# ST1S40IDR.net
KiCad netlist of a schematic drawn in Altium Designer
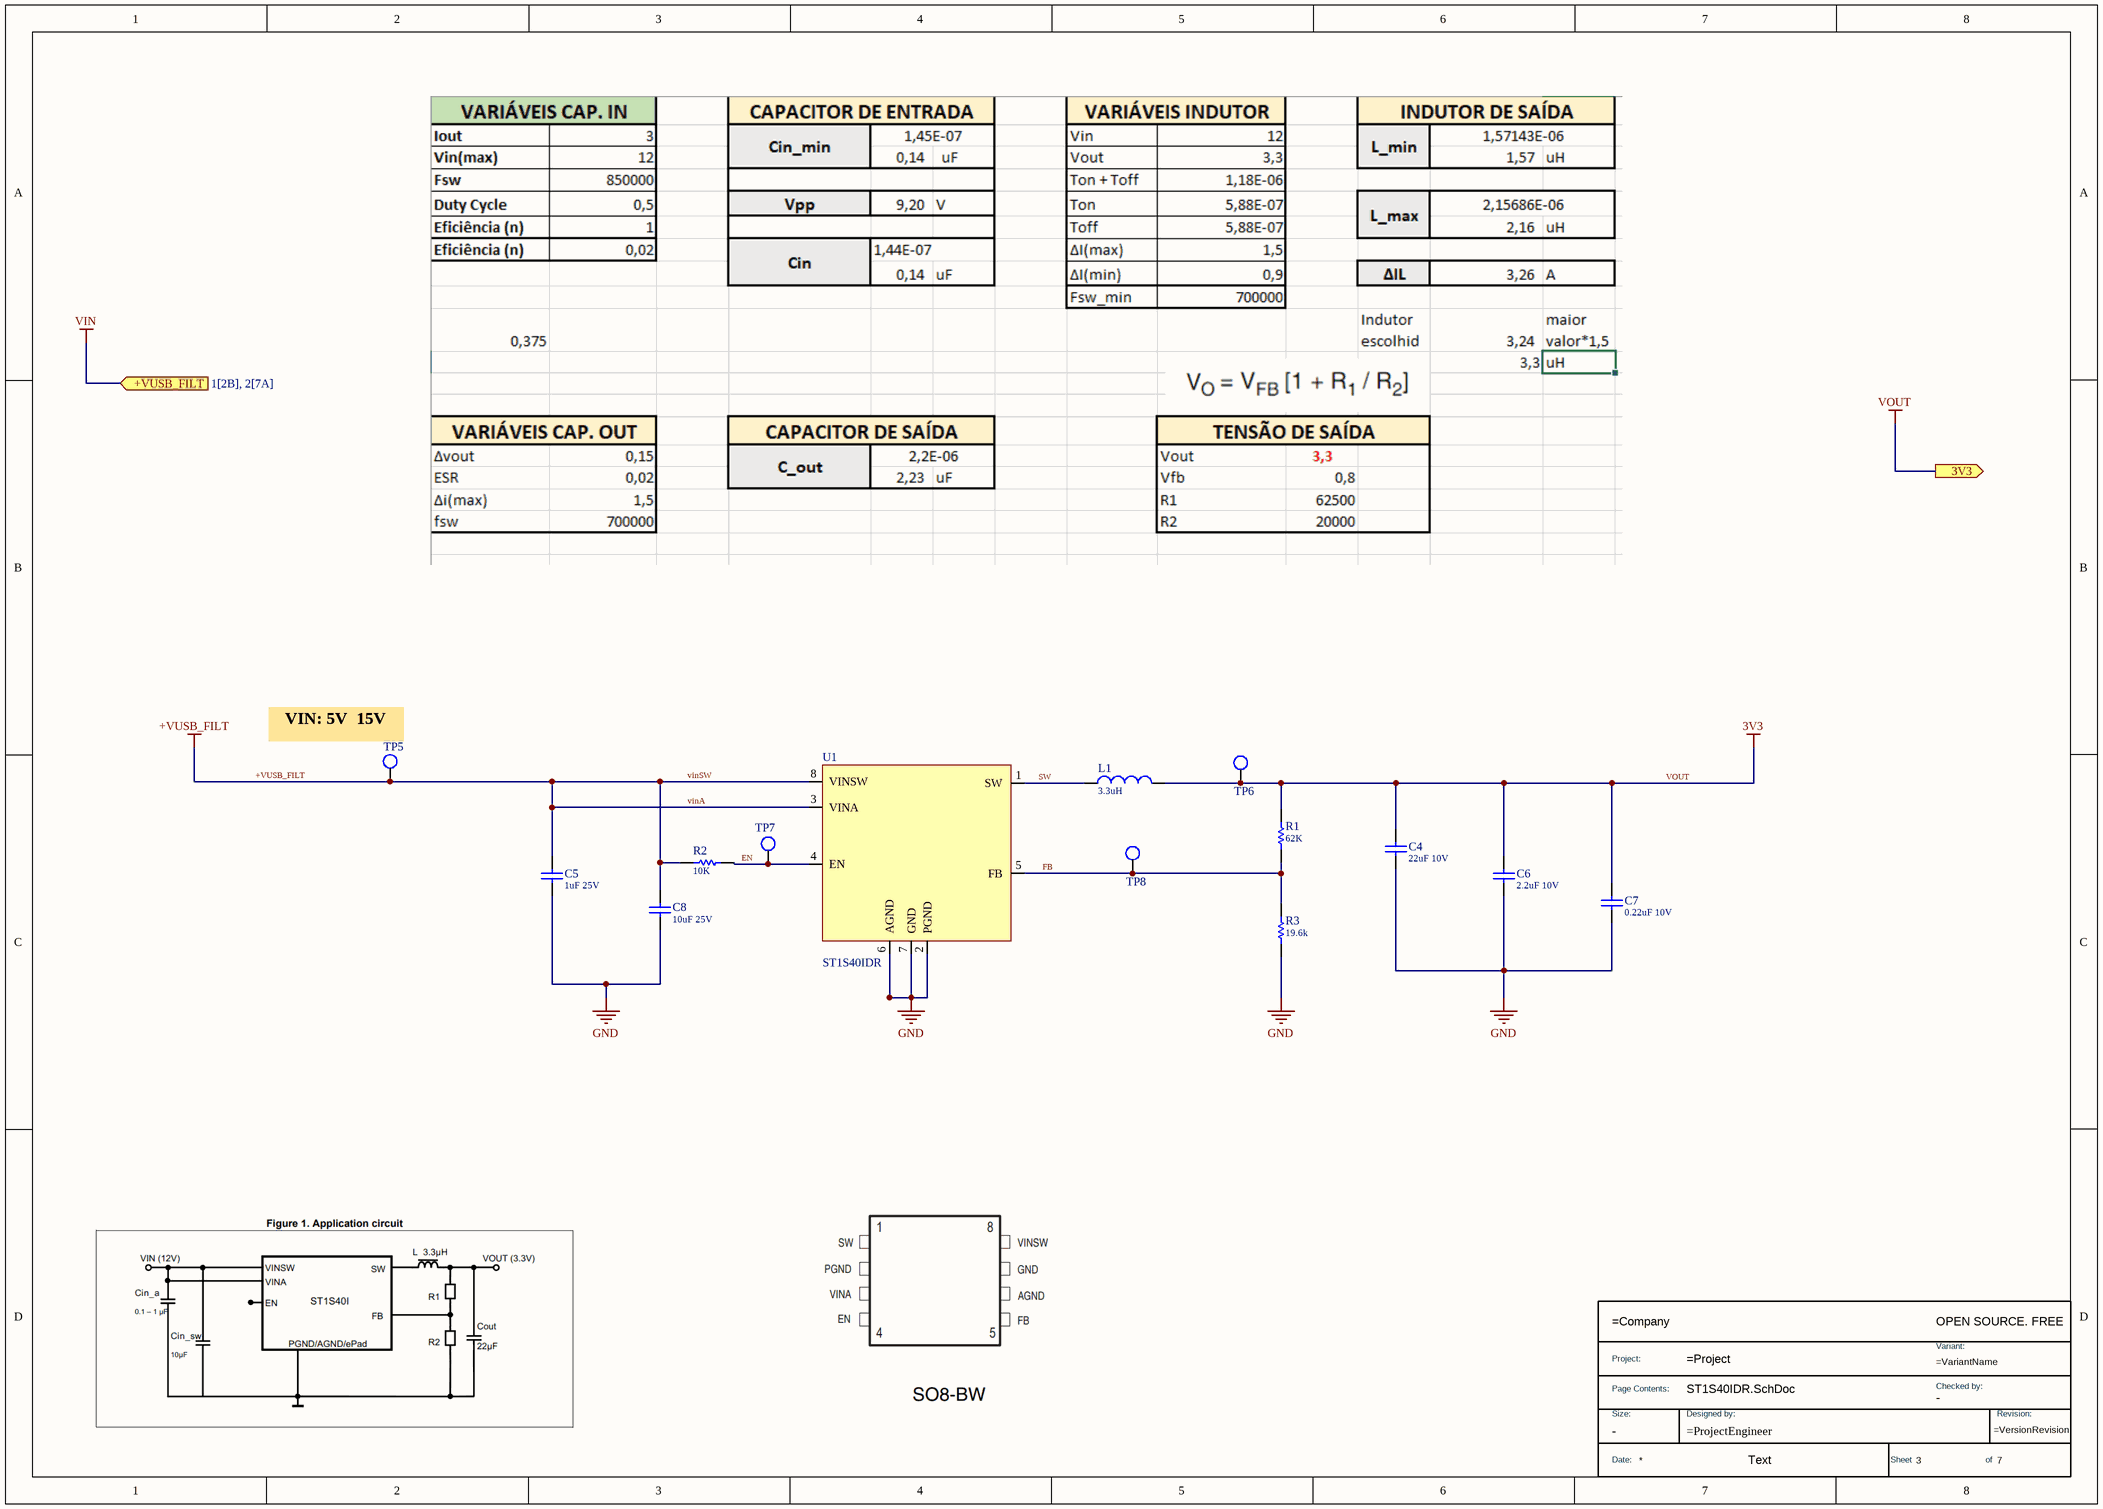
[diagram p0: ST1S40IDR.SchDoc]

(export (version "E")
  (design (tool "Eeschema 10.0.6"))
  (components
    (comp (ref "C4")
      (value "CL21A226MPQNNNE")
      (footprint "0805")
      (description "CAP CER 22UF 10V X5R 0805")
      (fields (field (name "MANUFACTURER") "Samsung Electro-Mechanics") (field (name "VALOR") "22uF 10V"))
      (libsource (lib "OBDH_Ed02") (part "CL21A226MPQNNNE"))
    )
    (comp (ref "C5")
      (value "CL21B105KAFNNNE")
      (footprint "CAP_0805")
      (description "CAP CER 1UF 25V X7R 0805")
      (fields (field (name "MANUFACTURER") "Samsung Electro-Mechanics") (field (name "VALOR") "1uF 25V"))
      (libsource (lib "OBDH_Ed02") (part "CL21B105KAFNNNE"))
    )
    (comp (ref "C6")
      (value "CL21B225KAFNNNE")
      (footprint "0805")
      (description "CAP CER 2.2UF 10V X5R 0805")
      (fields (field (name "MANUFACTURER") "Samsung Electro-Mechanics") (field (name "VALOR") "2.2uF 10V"))
      (libsource (lib "OBDH_Ed02") (part "CL21B225KAFNNNE"))
    )
    (comp (ref "C7")
      (value "CC0805KRX7R6BB224")
      (footprint "0805")
      (description "CAP CER 0.22uF 10V X5R 0805")
      (fields (field (name "MANUFACTURER") "YAGEO") (field (name "VALOR") "0.22uF 10V"))
      (libsource (lib "OBDH_Ed02") (part "CC0805KRX7R6BB224"))
    )
    (comp (ref "C8")
      (value "CL21A106KAYNNNE")
      (footprint "CAP_0805")
      (description "CAP CER 10UF 25V X5R 0805")
      (fields (field (name "MANUFACTURER") "Samsung Electro-Mechanics") (field (name "VALOR") "10uF 25V"))
      (libsource (lib "OBDH_Ed02") (part "CL21A106KAYNNNE"))
    )
    (comp (ref "L1")
      (value "3.3uH")
      (footprint "IND_6.1-4")
      (description "FIXED IND 3.3UH 4.2A 35.1MOHM SM")
      (fields (field (name "MANUFACTURER PART NUMBER") "VLS5045EX-3R3N-H"))
      (libsource (lib "OBDH_Ed02") (part "VLS5045EX-3R3N-H"))
    )
    (comp (ref "R1")
      (value "CRCW080562K0JNEA")
      (footprint "RES_0805")
      (description "RES SMD 62K OHM 5% 1/8W 0805")
      (fields (field (name "MANUFACTURER") "YAGEO") (field (name "VALOR") "62K"))
      (libsource (lib "OBDH_Ed02") (part "CRCW080562K0JNEA"))
    )
    (comp (ref "R2")
      (value "AF0805JR-0710KL")
      (footprint "RES_0805")
      (description "RES SMD 10K OHM 5% 1/8W 0805")
      (fields (field (name "MANUFACTURER") "YAGEO") (field (name "VALOR") "10K"))
      (libsource (lib "OBDH_Ed02") (part "AF0805JR-0710KL"))
    )
    (comp (ref "R3")
      (value "RT0805BRD0719K6L")
      (footprint "RES_0805")
      (description "RES SMD 19.6K OHM 5% 1/8W 0805")
      (fields (field (name "MANUFACTURER") "YAGEO") (field (name "VALOR") "19.6k"))
      (libsource (lib "OBDH_Ed02") (part "RT0805BRD0719K6L"))
    )
    (comp (ref "TP5")
      (value "TEST_POINT_1.5MM")
      (footprint "TESTPOINT_1.5MM")
      (description "TEST_POINT")
      (libsource (lib "OBDH_Ed02") (part "TEST_POINT_1.5MM"))
    )
    (comp (ref "TP6")
      (value "TEST_POINT_1.5MM")
      (footprint "TESTPOINT_1.5MM")
      (description "TEST_POINT")
      (libsource (lib "OBDH_Ed02") (part "TEST_POINT_1.5MM"))
    )
    (comp (ref "TP7")
      (value "TEST_POINT_1.5MM")
      (footprint "TESTPOINT_1.5MM")
      (description "TEST_POINT")
      (libsource (lib "OBDH_Ed02") (part "TEST_POINT_1.5MM"))
    )
    (comp (ref "TP8")
      (value "TEST_POINT_1.5MM")
      (footprint "TESTPOINT_1.5MM")
      (description "TEST_POINT")
      (libsource (lib "OBDH_Ed02") (part "TEST_POINT_1.5MM"))
    )
    (comp (ref "U1")
      (value "ST1S40IDR")
      (footprint "SO8-BW")
      (description "IC REG BUCK ADJUSTABLE 3A 8SO")
      (libsource (lib "OBDH_Ed02") (part "ST1S40IDR"))
    )
  )
  (nets
    (net (code "1") (name "+VUSB_FILT") (class "Default")
      (node (ref "C5") (pin "2") (pinfunction "2_2") (pintype "passive"))
      (node (ref "C8") (pin "1") (pinfunction "1_1") (pintype "passive"))
      (node (ref "R2") (pin "1") (pinfunction "1_1") (pintype "passive"))
      (node (ref "TP5") (pin "1") (pinfunction "1_1") (pintype "passive"))
      (node (ref "U1") (pin "3") (pinfunction "VINA_3") (pintype "passive"))
      (node (ref "U1") (pin "8") (pinfunction "VINSW_8") (pintype "passive"))
    )
    (net (code "2") (name "/EN") (class "Default")
      (node (ref "R2") (pin "2") (pinfunction "2_2") (pintype "passive"))
      (node (ref "TP7") (pin "1") (pinfunction "1_1") (pintype "passive"))
      (node (ref "U1") (pin "4") (pinfunction "EN_4") (pintype "passive"))
    )
    (net (code "3") (name "/FB") (class "Default")
      (node (ref "R1") (pin "1") (pinfunction "1_1") (pintype "passive"))
      (node (ref "R3") (pin "2") (pinfunction "2_2") (pintype "passive"))
      (node (ref "TP8") (pin "1") (pinfunction "1_1") (pintype "passive"))
      (node (ref "U1") (pin "5") (pinfunction "FB_5") (pintype "passive"))
    )
    (net (code "4") (name "/SW") (class "Default")
      (node (ref "L1") (pin "1") (pinfunction "1_1") (pintype "passive"))
      (node (ref "U1") (pin "1") (pinfunction "SW_1") (pintype "passive"))
    )
    (net (code "5") (name "3V3") (class "Default")
      (node (ref "C4") (pin "2") (pinfunction "2_2") (pintype "passive"))
      (node (ref "C6") (pin "2") (pinfunction "2_2") (pintype "passive"))
      (node (ref "C7") (pin "2") (pinfunction "2_2") (pintype "passive"))
      (node (ref "L1") (pin "2") (pinfunction "2_2") (pintype "passive"))
      (node (ref "R1") (pin "2") (pinfunction "2_2") (pintype "passive"))
      (node (ref "TP6") (pin "1") (pinfunction "1_1") (pintype "passive"))
    )
    (net (code "6") (name "GND") (class "Default")
      (node (ref "C4") (pin "1") (pinfunction "1_1") (pintype "passive"))
      (node (ref "C5") (pin "1") (pinfunction "1_1") (pintype "passive"))
      (node (ref "C6") (pin "1") (pinfunction "1_1") (pintype "passive"))
      (node (ref "C7") (pin "1") (pinfunction "1_1") (pintype "passive"))
      (node (ref "C8") (pin "2") (pinfunction "2_2") (pintype "passive"))
      (node (ref "R3") (pin "1") (pinfunction "1_1") (pintype "passive"))
      (node (ref "U1") (pin "2") (pinfunction "PGND_2") (pintype "passive"))
      (node (ref "U1") (pin "6") (pinfunction "AGND_6") (pintype "passive"))
      (node (ref "U1") (pin "7") (pinfunction "GND_7") (pintype "passive"))
    )
  )
)
